# IOTERM.net
KiCad netlist of a schematic drawn in EAGLE
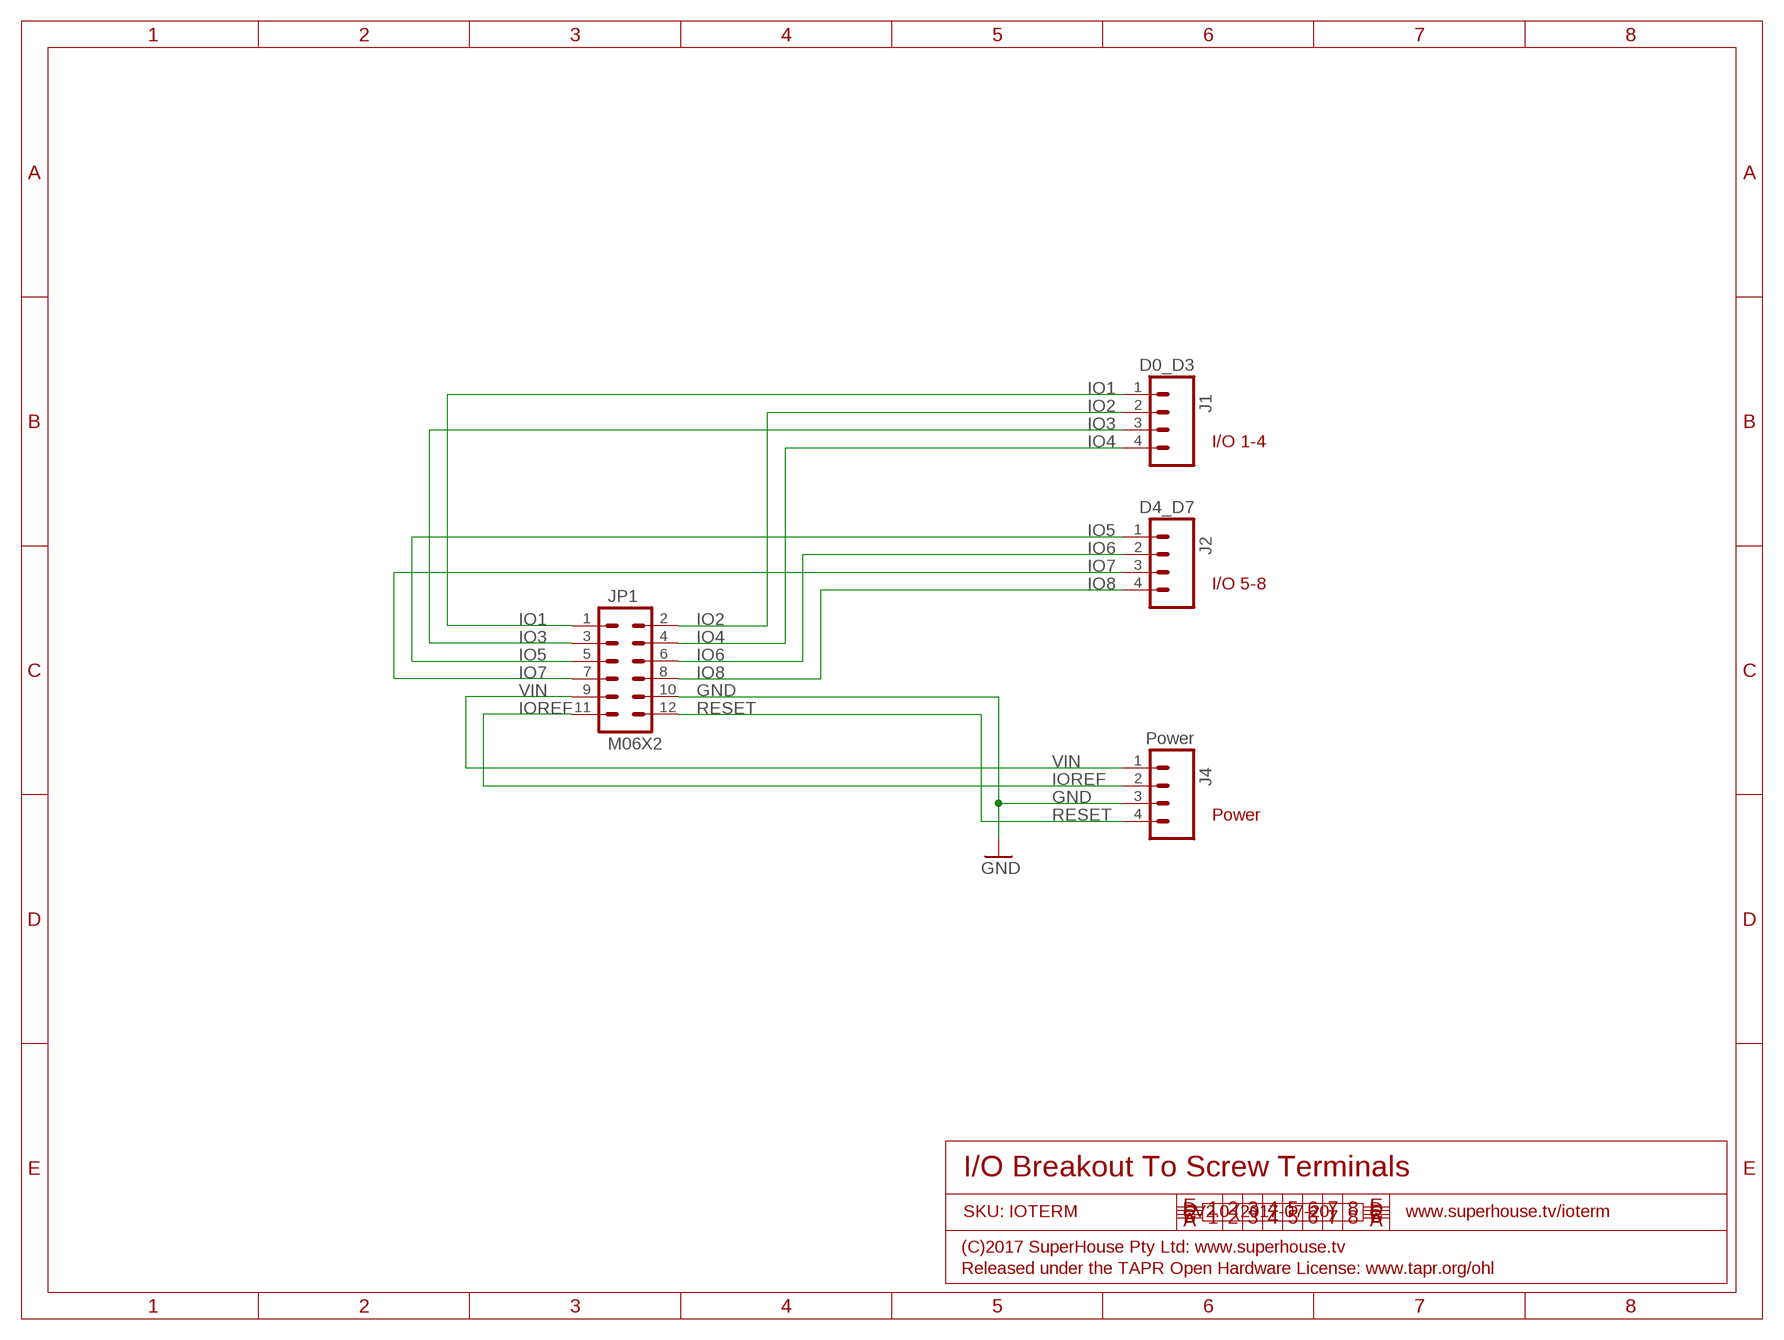
[diagram p0: schematic, sheet 1]

(export (version "E")
  (design (tool "Eeschema 10.0.6"))
  (components
    (comp (ref "J1")
      (value "D0_D3")
      (footprint "eagle-import:SCREWTERMINAL-3.5MM-4")
      (libsource (lib "eagle-import") (part "M04SCREW"))
    )
    (comp (ref "J2")
      (value "D4_D7")
      (footprint "eagle-import:SCREWTERMINAL-3.5MM-4")
      (libsource (lib "eagle-import") (part "M04SCREW"))
    )
    (comp (ref "J4")
      (value "Power")
      (footprint "eagle-import:SCREWTERMINAL-3.5MM-4")
      (libsource (lib "eagle-import") (part "M04SCREW"))
    )
    (comp (ref "JP1")
      (value "M06X2")
      (footprint "eagle-import:2X6-SHROUDED")
      (libsource (lib "eagle-import") (part "M06X2"))
    )
  )
  (nets
    (net (code "1") (name "/IO1") (class "Default")
      (node (ref "J1") (pin "1") (pinfunction "1_1") (pintype "passive"))
      (node (ref "JP1") (pin "1") (pinfunction "1_1") (pintype "passive"))
    )
    (net (code "2") (name "/IO2") (class "Default")
      (node (ref "J1") (pin "2") (pinfunction "2_2") (pintype "passive"))
      (node (ref "JP1") (pin "2") (pinfunction "2_2") (pintype "passive"))
    )
    (net (code "3") (name "/IO3") (class "Default")
      (node (ref "J1") (pin "3") (pinfunction "3_3") (pintype "passive"))
      (node (ref "JP1") (pin "3") (pinfunction "3_3") (pintype "passive"))
    )
    (net (code "4") (name "/IO4") (class "Default")
      (node (ref "J1") (pin "4") (pinfunction "4_4") (pintype "passive"))
      (node (ref "JP1") (pin "4") (pinfunction "4_4") (pintype "passive"))
    )
    (net (code "5") (name "/IO5") (class "Default")
      (node (ref "J2") (pin "1") (pinfunction "1_1") (pintype "passive"))
      (node (ref "JP1") (pin "5") (pinfunction "5_5") (pintype "passive"))
    )
    (net (code "6") (name "/IO6") (class "Default")
      (node (ref "J2") (pin "2") (pinfunction "2_2") (pintype "passive"))
      (node (ref "JP1") (pin "6") (pinfunction "6_6") (pintype "passive"))
    )
    (net (code "7") (name "/IO7") (class "Default")
      (node (ref "J2") (pin "3") (pinfunction "3_3") (pintype "passive"))
      (node (ref "JP1") (pin "7") (pinfunction "7_7") (pintype "passive"))
    )
    (net (code "8") (name "/IO8") (class "Default")
      (node (ref "J2") (pin "4") (pinfunction "4_4") (pintype "passive"))
      (node (ref "JP1") (pin "8") (pinfunction "8_8") (pintype "passive"))
    )
    (net (code "9") (name "/IOREF") (class "Default")
      (node (ref "J4") (pin "2") (pinfunction "2_2") (pintype "passive"))
      (node (ref "JP1") (pin "11") (pinfunction "11_11") (pintype "passive"))
    )
    (net (code "10") (name "/RESET") (class "Default")
      (node (ref "J4") (pin "4") (pinfunction "4_4") (pintype "passive"))
      (node (ref "JP1") (pin "12") (pinfunction "12_12") (pintype "passive"))
    )
    (net (code "11") (name "/VIN") (class "Default")
      (node (ref "J4") (pin "1") (pinfunction "1_1") (pintype "passive"))
      (node (ref "JP1") (pin "9") (pinfunction "9_9") (pintype "passive"))
    )
    (net (code "12") (name "GND") (class "Default")
      (node (ref "J4") (pin "3") (pinfunction "3_3") (pintype "passive"))
      (node (ref "JP1") (pin "10") (pinfunction "10_10") (pintype "passive"))
    )
  )
)
